# TB-S5D5_p05_JLink_OB-S124_QFP-v1_2.net
KiCad netlist of a schematic drawn in Altium Designer
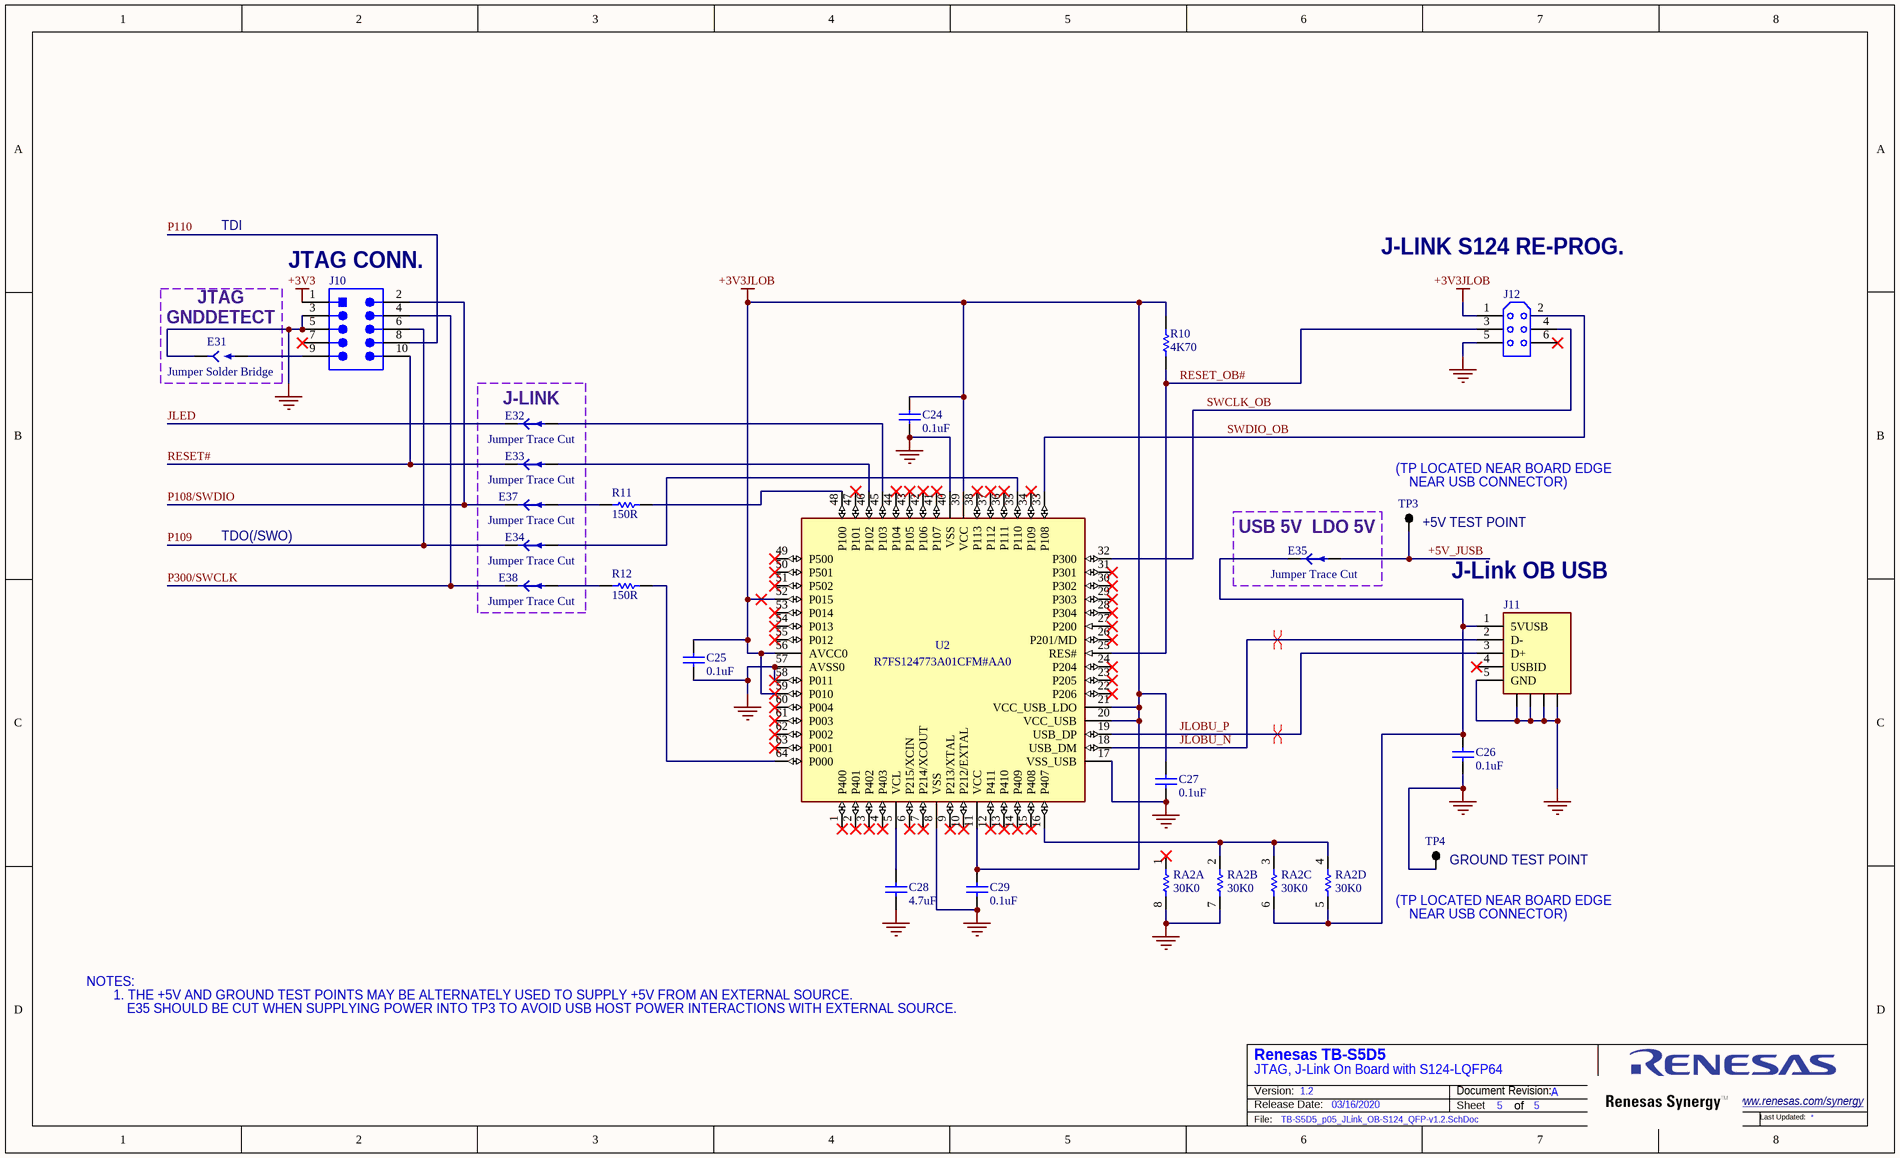
[diagram p0: TB-S5D5_p05_JLink_OB-S124_QFP-v1.2.SchDoc]

(export (version "E")
  (design (tool "Eeschema 10.0.6"))
  (components
    (comp (ref "C24")
      (value "CAP-000029-01")
      (footprint "CAPC0603-01")
      (description "Ceramic Chip Capacitor 0603 0.1uF 50V")
      (fields
        (field (name "MANUFACTURER") "Samsung")
        (field (name "MFG PART NUMBER") "CL10B104KB8NNNC")
        (field (name "CAPACITANCE") "0.1uF")
      )
      (libsource (lib "Capacitors") (part "CAP-000029-01"))
    )
    (comp (ref "C25")
      (value "CAP-000029-01")
      (footprint "CAPC0603-01")
      (description "Ceramic Chip Capacitor 0603 0.1uF 50V")
      (fields
        (field (name "MANUFACTURER") "Samsung")
        (field (name "MFG PART NUMBER") "CL10B104KB8NNNC")
        (field (name "CAPACITANCE") "0.1uF")
      )
      (libsource (lib "Capacitors") (part "CAP-000029-01"))
    )
    (comp (ref "C26")
      (value "CAP-000029-01")
      (footprint "CAPC0603-01")
      (description "Ceramic Chip Capacitor 0603 0.1uF 50V")
      (fields
        (field (name "MANUFACTURER") "Samsung")
        (field (name "MFG PART NUMBER") "CL10B104KB8NNNC")
        (field (name "CAPACITANCE") "0.1uF")
      )
      (libsource (lib "Capacitors") (part "CAP-000029-01"))
    )
    (comp (ref "C27")
      (value "CAP-000029-01")
      (footprint "CAPC0603-01")
      (description "Ceramic Chip Capacitor 0603 0.1uF 50V")
      (fields
        (field (name "MANUFACTURER") "Samsung")
        (field (name "MFG PART NUMBER") "CL10B104KB8NNNC")
        (field (name "CAPACITANCE") "0.1uF")
      )
      (libsource (lib "Capacitors") (part "CAP-000029-01"))
    )
    (comp (ref "C28")
      (value "CAP-000043-01")
      (footprint "CAPC0603-01")
      (description "Ceramic Chip Capacitor 0603 4.7uF 6.3V")
      (fields
        (field (name "MANUFACTURER") "Samsung")
        (field (name "MFG PART NUMBER") "CL10A475KQ8NNNL")
        (field (name "CAPACITANCE") "4.7uF")
      )
      (libsource (lib "Capacitors") (part "CAP-000043-01"))
    )
    (comp (ref "C29")
      (value "CAP-000029-01")
      (footprint "CAPC0603-01")
      (description "Ceramic Chip Capacitor 0603 0.1uF 50V")
      (fields
        (field (name "MANUFACTURER") "Samsung")
        (field (name "MFG PART NUMBER") "CL10B104KB8NNNC")
        (field (name "CAPACITANCE") "0.1uF")
      )
      (libsource (lib "Capacitors") (part "CAP-000029-01"))
    )
    (comp (ref "E31")
      (value "Jumper Solder Bridge")
      (footprint "E_PadsSplit0805")
      (description "Pads on PCB with Narrow Gap to allow Solder Bridging")
      (libsource (lib "TB_SpecialLib") (part "E_JmpSldrBridge"))
    )
    (comp (ref "E32")
      (value "Jumper Trace Cut")
      (footprint "E_PadsTraceCut0805")
      (description "Pads on PCB with Trace Between for Cutting to isolate")
      (libsource (lib "TB_SpecialLib") (part "E_JmpTraceCut"))
    )
    (comp (ref "E33")
      (value "Jumper Trace Cut")
      (footprint "E_PadsTraceCut0805")
      (description "Pads on PCB with Trace Between for Cutting to isolate")
      (libsource (lib "TB_SpecialLib") (part "E_JmpTraceCut"))
    )
    (comp (ref "E34")
      (value "Jumper Trace Cut")
      (footprint "E_PadsTraceCut0805")
      (description "Pads on PCB with Trace Between for Cutting to isolate")
      (libsource (lib "TB_SpecialLib") (part "E_JmpTraceCut"))
    )
    (comp (ref "E35")
      (value "Jumper Trace Cut")
      (footprint "E_PadsTraceCut0805")
      (description "Pads on PCB with Trace Between for Cutting to isolate")
      (libsource (lib "TB_SpecialLib") (part "E_JmpTraceCut"))
    )
    (comp (ref "E37")
      (value "Jumper Trace Cut")
      (footprint "E_PadsTraceCut0805")
      (description "Pads on PCB with Trace Between for Cutting to isolate")
      (libsource (lib "TB_SpecialLib") (part "E_JmpTraceCut"))
    )
    (comp (ref "E38")
      (value "Jumper Trace Cut")
      (footprint "E_PadsTraceCut0805")
      (description "Pads on PCB with Trace Between for Cutting to isolate")
      (libsource (lib "TB_SpecialLib") (part "E_JmpTraceCut"))
    )
    (comp (ref "J10")
      (value "CON-REN001-01")
      (footprint "J_10pTH2cx5r")
      (description "10 Position Shrouded Header 1.27mm Pitch")
      (fields (field (name "MANUFACTURER") "CNC Tech") (field (name "MFG PART NUMBER") "3220-10-0100-00"))
      (libsource (lib "SpecialPartsLib") (part "CON-REN001-01"))
    )
    (comp (ref "J11")
      (value "CON-000116-01")
      (footprint "FCI_10118192")
      (description "USB Micro 2.0 Female 5 Pin Right Angle")
      (fields (field (name "MANUFACTURER") "FCI") (field (name "MFG PART NUMBER") "10118192-0001LF"))
      (libsource (lib "Connectors") (part "CON-000116-01"))
    )
    (comp (ref "J12")
      (value "CON-000241-01")
      (footprint "TC2030NL")
      (description "Tag Connect TC-2030 PCB Pads 6 Pos 2x3")
      (libsource (lib "Connectors") (part "CON-000241-01"))
    )
    (comp (ref "R10")
      (value "RES-000127-01")
      (footprint "RESC0402-01")
      (description "Chip Resistor Thick Film 0402 4K70 0.5% 1/16W")
      (fields
        (field (name "MANUFACTURER") "Panasonic")
        (field (name "MFG PART NUMBER") "ERA-2AED472X")
        (field (name "RESISTANCE") "4K70")
      )
      (libsource (lib "Resistors") (part "RES-000127-01"))
    )
    (comp (ref "R11")
      (value "RES-000220-01")
      (footprint "RESC0402-01")
      (description "Chip Resistor Thick Film 0402 150R 1% 1/10W")
      (fields
        (field (name "MANUFACTURER") "Panasonic")
        (field (name "MFG PART NUMBER") "ERJ-2RKF1500X")
        (field (name "RESISTANCE") "150R")
      )
      (libsource (lib "Resistors") (part "RES-000220-01"))
    )
    (comp (ref "R12")
      (value "RES-000220-01")
      (footprint "RESC0402-01")
      (description "Chip Resistor Thick Film 0402 150R 1% 1/10W")
      (fields
        (field (name "MANUFACTURER") "Panasonic")
        (field (name "MFG PART NUMBER") "ERJ-2RKF1500X")
        (field (name "RESISTANCE") "150R")
      )
      (libsource (lib "Resistors") (part "RES-000220-01"))
    )
    (comp (ref "RA2")
      (value "RES-000117-01")
      (footprint "RESCAF0804")
      (description "Chip Resistor Array 0804 30K0 5% 1/16W 4 x 0402")
      (fields
        (field (name "MANUFACTURER") "Panasonic")
        (field (name "MFG PART NUMBER") "EXB-28V303JX")
        (field (name "RESISTANCE") "30K0")
      )
      (libsource (lib "Resistors") (part "RES-000117-01"))
    )
    (comp (ref "TP3")
      (value "Test Point")
      (footprint "TP_40milTHpad")
      (description "Test Point, Through Hole Pad 40mil ID")
      (libsource (lib "TB_SpecialLib") (part "TP_TH"))
    )
    (comp (ref "TP4")
      (value "Test Point")
      (footprint "TP_40milTHpad")
      (description "Test Point, Through Hole Pad 40mil ID")
      (libsource (lib "TB_SpecialLib") (part "TP_TH"))
    )
    (comp (ref "U2")
      (value "ICN-000202-01")
      (footprint "RENESAS_PLQP0064KB-A_N")
      (description "Renesas S124 32-Bit 32MHz Cortex M0+ MCU LQFP64")
      (fields
        (field (name "MANUFACTURER") "Renesas")
        (field (name "MFG PART NUMBER") "R7FS124773A01CFM#AA0")
        (field (name "DISPLAY NAME") "R7FS124773A01CFM#AA0")
      )
      (libsource (lib "IC_MCU") (part "ICN-000202-01"))
    )
  )
  (nets
    (net (code "1") (name "+3V3") (class "Default")
      (node (ref "J10") (pin "1") (pinfunction "1_1") (pintype "passive"))
    )
    (net (code "2") (name "+3V3JLOB") (class "Default")
      (node (ref "C24") (pin "2") (pinfunction "2_2") (pintype "passive"))
      (node (ref "C25") (pin "2") (pinfunction "2_2") (pintype "passive"))
      (node (ref "C27") (pin "2") (pinfunction "2_2") (pintype "passive"))
      (node (ref "C29") (pin "2") (pinfunction "2_2") (pintype "passive"))
      (node (ref "J12") (pin "1") (pinfunction "1_1") (pintype "passive"))
      (node (ref "R10") (pin "2") (pinfunction "2_2") (pintype "passive"))
      (node (ref "U2") (pin "11") (pinfunction "VCC_11") (pintype "power_in"))
      (node (ref "U2") (pin "20") (pinfunction "VCC_USB_20") (pintype "power_in"))
      (node (ref "U2") (pin "21") (pinfunction "VCC_USB_LDO_21") (pintype "power_in"))
      (node (ref "U2") (pin "39") (pinfunction "VCC_39") (pintype "power_in"))
      (node (ref "U2") (pin "52") (pinfunction "P015_52") (pintype "bidirectional"))
      (node (ref "U2") (pin "56") (pinfunction "AVCC0_56") (pintype "power_in"))
      (node (ref "U2") (pin "59") (pinfunction "P010_59") (pintype "bidirectional"))
    )
    (net (code "3") (name "/+5V_JUSB") (class "Default")
      (node (ref "E35") (pin "2") (pinfunction "A_2") (pintype "passive"))
      (node (ref "TP3") (pin "1") (pinfunction "TP_1") (pintype "passive"))
    )
    (net (code "4") (name "/JLED") (class "Default")
      (node (ref "E32") (pin "1") (pinfunction "A_1") (pintype "passive"))
    )
    (net (code "5") (name "/JLOBU_N") (class "Default")
      (node (ref "J11") (pin "2") (pinfunction "D-_2") (pintype "passive"))
      (node (ref "U2") (pin "18") (pinfunction "USB_DM_18") (pintype "bidirectional"))
    )
    (net (code "6") (name "/JLOBU_P") (class "Default")
      (node (ref "J11") (pin "3") (pinfunction "D+_3") (pintype "passive"))
      (node (ref "U2") (pin "19") (pinfunction "USB_DP_19") (pintype "bidirectional"))
    )
    (net (code "7") (name "/P108{slash}SWDIO") (class "Default")
      (node (ref "E37") (pin "1") (pinfunction "A_1") (pintype "passive"))
      (node (ref "J10") (pin "2") (pinfunction "2_2") (pintype "passive"))
    )
    (net (code "8") (name "/P109") (class "Default")
      (node (ref "E34") (pin "1") (pinfunction "A_1") (pintype "passive"))
      (node (ref "J10") (pin "6") (pinfunction "6_6") (pintype "passive"))
    )
    (net (code "9") (name "/P110") (class "Default")
      (node (ref "J10") (pin "8") (pinfunction "8_8") (pintype "passive"))
    )
    (net (code "10") (name "/P300{slash}SWCLK") (class "Default")
      (node (ref "E38") (pin "1") (pinfunction "A_1") (pintype "passive"))
      (node (ref "J10") (pin "4") (pinfunction "4_4") (pintype "passive"))
    )
    (net (code "11") (name "/RESET#") (class "Default")
      (node (ref "E33") (pin "1") (pinfunction "A_1") (pintype "passive"))
      (node (ref "J10") (pin "10") (pinfunction "10_10") (pintype "passive"))
    )
    (net (code "12") (name "/RESET_OB#") (class "Default")
      (node (ref "J12") (pin "3") (pinfunction "3_3") (pintype "passive"))
      (node (ref "R10") (pin "1") (pinfunction "1_1") (pintype "passive"))
      (node (ref "U2") (pin "25") (pinfunction "RES#_25") (pintype "input"))
    )
    (net (code "13") (name "/SWCLK_OB") (class "Default")
      (node (ref "J12") (pin "4") (pinfunction "4_4") (pintype "passive"))
      (node (ref "U2") (pin "32") (pinfunction "P300_32") (pintype "bidirectional"))
    )
    (net (code "14") (name "/SWDIO_OB") (class "Default")
      (node (ref "J12") (pin "2") (pinfunction "2_2") (pintype "passive"))
      (node (ref "U2") (pin "33") (pinfunction "P108_33") (pintype "bidirectional"))
    )
    (net (code "15") (name "GND") (class "Default")
      (node (ref "C24") (pin "1") (pinfunction "1_1") (pintype "passive"))
      (node (ref "C25") (pin "1") (pinfunction "1_1") (pintype "passive"))
      (node (ref "C26") (pin "1") (pinfunction "1_1") (pintype "passive"))
      (node (ref "C27") (pin "1") (pinfunction "1_1") (pintype "passive"))
      (node (ref "C28") (pin "2") (pinfunction "2_2") (pintype "passive"))
      (node (ref "C29") (pin "1") (pinfunction "1_1") (pintype "passive"))
      (node (ref "E31") (pin "1") (pinfunction "A_1") (pintype "passive"))
      (node (ref "J10") (pin "3") (pinfunction "3_3") (pintype "passive"))
      (node (ref "J10") (pin "5") (pinfunction "5_5") (pintype "passive"))
      (node (ref "J11") (pin "5") (pinfunction "GND_5") (pintype "passive"))
      (node (ref "J11") (pin "C1") (pinfunction "C1_C1") (pintype "passive"))
      (node (ref "J11") (pin "C2") (pinfunction "C2_C2") (pintype "passive"))
      (node (ref "J11") (pin "C3") (pinfunction "C3_C3") (pintype "passive"))
      (node (ref "J11") (pin "C4") (pinfunction "C4_C4") (pintype "passive"))
      (node (ref "J12") (pin "5") (pinfunction "5_5") (pintype "passive"))
      (node (ref "RA2") (pin "7") (pinfunction "7_7") (pintype "passive"))
      (node (ref "RA2") (pin "8") (pinfunction "8_8") (pintype "passive"))
      (node (ref "TP4") (pin "1") (pinfunction "TP_1") (pintype "passive"))
      (node (ref "U2") (pin "17") (pinfunction "VSS_USB_17") (pintype "power_in"))
      (node (ref "U2") (pin "40") (pinfunction "VSS_40") (pintype "power_in"))
      (node (ref "U2") (pin "57") (pinfunction "AVSS0_57") (pintype "power_in"))
      (node (ref "U2") (pin "58") (pinfunction "P011_58") (pintype "bidirectional"))
      (node (ref "U2") (pin "8") (pinfunction "VSS_8") (pintype "power_in"))
    )
    (net (code "16") (name "Net-(E31-A-Pad2)") (class "Default")
      (node (ref "E31") (pin "2") (pinfunction "A_2") (pintype "passive"))
      (node (ref "J10") (pin "9") (pinfunction "9_9") (pintype "passive"))
    )
    (net (code "17") (name "Net-(E37-A-Pad2)") (class "Default")
      (node (ref "E37") (pin "2") (pinfunction "A_2") (pintype "passive"))
      (node (ref "R11") (pin "1") (pinfunction "1_1") (pintype "passive"))
    )
    (net (code "18") (name "Net-(E38-A-Pad2)") (class "Default")
      (node (ref "E38") (pin "2") (pinfunction "A_2") (pintype "passive"))
      (node (ref "R12") (pin "1") (pinfunction "1_1") (pintype "passive"))
    )
    (net (code "19") (name "Net-(J11-5VUSB)") (class "Default")
      (node (ref "C26") (pin "2") (pinfunction "2_2") (pintype "passive"))
      (node (ref "E35") (pin "1") (pinfunction "A_1") (pintype "passive"))
      (node (ref "J11") (pin "1") (pinfunction "5VUSB_1") (pintype "passive"))
      (node (ref "RA2") (pin "5") (pinfunction "5_5") (pintype "passive"))
      (node (ref "RA2") (pin "6") (pinfunction "6_6") (pintype "passive"))
    )
    (net (code "20") (name "Net-(U2-P000)") (class "Default")
      (node (ref "R12") (pin "2") (pinfunction "2_2") (pintype "passive"))
      (node (ref "U2") (pin "64") (pinfunction "P000_64") (pintype "bidirectional"))
    )
    (net (code "21") (name "Net-(U2-P100)") (class "Default")
      (node (ref "R11") (pin "2") (pinfunction "2_2") (pintype "passive"))
      (node (ref "U2") (pin "48") (pinfunction "P100_48") (pintype "bidirectional"))
    )
    (net (code "22") (name "Net-(U2-P102)") (class "Default")
      (node (ref "E33") (pin "2") (pinfunction "A_2") (pintype "passive"))
      (node (ref "U2") (pin "46") (pinfunction "P102_46") (pintype "bidirectional"))
    )
    (net (code "23") (name "Net-(U2-P103)") (class "Default")
      (node (ref "E32") (pin "2") (pinfunction "A_2") (pintype "passive"))
      (node (ref "U2") (pin "45") (pinfunction "P103_45") (pintype "bidirectional"))
    )
    (net (code "24") (name "Net-(U2-P110)") (class "Default")
      (node (ref "E34") (pin "2") (pinfunction "A_2") (pintype "passive"))
      (node (ref "U2") (pin "35") (pinfunction "P110_35") (pintype "bidirectional"))
    )
    (net (code "25") (name "Net-(U2-P407)") (class "Default")
      (node (ref "RA2") (pin "2") (pinfunction "2_2") (pintype "passive"))
      (node (ref "RA2") (pin "3") (pinfunction "3_3") (pintype "passive"))
      (node (ref "RA2") (pin "4") (pinfunction "4_4") (pintype "passive"))
      (node (ref "U2") (pin "16") (pinfunction "P407_16") (pintype "bidirectional"))
    )
    (net (code "26") (name "Net-(U2-VCL)") (class "Default")
      (node (ref "C28") (pin "1") (pinfunction "1_1") (pintype "passive"))
      (node (ref "U2") (pin "5") (pinfunction "VCL_5") (pintype "passive"))
    )
    (net (code "27") (name "unconnected-(J10-Pad7)") (class "Default")
      (node (ref "J10") (pin "7") (pinfunction "7_7") (pintype "passive+no_connect"))
    )
    (net (code "28") (name "unconnected-(J11-USBID-Pad4)") (class "Default")
      (node (ref "J11") (pin "4") (pinfunction "USBID_4") (pintype "passive+no_connect"))
    )
    (net (code "29") (name "unconnected-(J12-Pad6)") (class "Default")
      (node (ref "J12") (pin "6") (pinfunction "6_6") (pintype "passive+no_connect"))
    )
    (net (code "30") (name "unconnected-(RA2-Pad1)") (class "Default")
      (node (ref "RA2") (pin "1") (pinfunction "1_1") (pintype "passive+no_connect"))
    )
    (net (code "31") (name "unconnected-(U2-P001-Pad63)") (class "Default")
      (node (ref "U2") (pin "63") (pinfunction "P001_63") (pintype "bidirectional+no_connect"))
    )
    (net (code "32") (name "unconnected-(U2-P002-Pad62)") (class "Default")
      (node (ref "U2") (pin "62") (pinfunction "P002_62") (pintype "bidirectional+no_connect"))
    )
    (net (code "33") (name "unconnected-(U2-P003-Pad61)") (class "Default")
      (node (ref "U2") (pin "61") (pinfunction "P003_61") (pintype "bidirectional+no_connect"))
    )
    (net (code "34") (name "unconnected-(U2-P004-Pad60)") (class "Default")
      (node (ref "U2") (pin "60") (pinfunction "P004_60") (pintype "bidirectional+no_connect"))
    )
    (net (code "35") (name "unconnected-(U2-P012-Pad55)") (class "Default")
      (node (ref "U2") (pin "55") (pinfunction "P012_55") (pintype "bidirectional+no_connect"))
    )
    (net (code "36") (name "unconnected-(U2-P013-Pad54)") (class "Default")
      (node (ref "U2") (pin "54") (pinfunction "P013_54") (pintype "bidirectional+no_connect"))
    )
    (net (code "37") (name "unconnected-(U2-P014-Pad53)") (class "Default")
      (node (ref "U2") (pin "53") (pinfunction "P014_53") (pintype "bidirectional+no_connect"))
    )
    (net (code "38") (name "unconnected-(U2-P101-Pad47)") (class "Default")
      (node (ref "U2") (pin "47") (pinfunction "P101_47") (pintype "bidirectional+no_connect"))
    )
    (net (code "39") (name "unconnected-(U2-P104-Pad44)") (class "Default")
      (node (ref "U2") (pin "44") (pinfunction "P104_44") (pintype "bidirectional+no_connect"))
    )
    (net (code "40") (name "unconnected-(U2-P105-Pad43)") (class "Default")
      (node (ref "U2") (pin "43") (pinfunction "P105_43") (pintype "bidirectional+no_connect"))
    )
    (net (code "41") (name "unconnected-(U2-P106-Pad42)") (class "Default")
      (node (ref "U2") (pin "42") (pinfunction "P106_42") (pintype "bidirectional+no_connect"))
    )
    (net (code "42") (name "unconnected-(U2-P107-Pad41)") (class "Default")
      (node (ref "U2") (pin "41") (pinfunction "P107_41") (pintype "bidirectional+no_connect"))
    )
    (net (code "43") (name "unconnected-(U2-P109-Pad34)") (class "Default")
      (node (ref "U2") (pin "34") (pinfunction "P109_34") (pintype "bidirectional+no_connect"))
    )
    (net (code "44") (name "unconnected-(U2-P111-Pad36)") (class "Default")
      (node (ref "U2") (pin "36") (pinfunction "P111_36") (pintype "bidirectional+no_connect"))
    )
    (net (code "45") (name "unconnected-(U2-P112-Pad37)") (class "Default")
      (node (ref "U2") (pin "37") (pinfunction "P112_37") (pintype "bidirectional+no_connect"))
    )
    (net (code "46") (name "unconnected-(U2-P113-Pad38)") (class "Default")
      (node (ref "U2") (pin "38") (pinfunction "P113_38") (pintype "bidirectional+no_connect"))
    )
    (net (code "47") (name "unconnected-(U2-P200-Pad27)") (class "Default")
      (node (ref "U2") (pin "27") (pinfunction "P200_27") (pintype "input+no_connect"))
    )
    (net (code "48") (name "unconnected-(U2-P201{slash}MD-Pad26)") (class "Default")
      (node (ref "U2") (pin "26") (pinfunction "P201/MD_26") (pintype "bidirectional+no_connect"))
    )
    (net (code "49") (name "unconnected-(U2-P204-Pad24)") (class "Default")
      (node (ref "U2") (pin "24") (pinfunction "P204_24") (pintype "bidirectional+no_connect"))
    )
    (net (code "50") (name "unconnected-(U2-P205-Pad23)") (class "Default")
      (node (ref "U2") (pin "23") (pinfunction "P205_23") (pintype "bidirectional+no_connect"))
    )
    (net (code "51") (name "unconnected-(U2-P206-Pad22)") (class "Default")
      (node (ref "U2") (pin "22") (pinfunction "P206_22") (pintype "bidirectional+no_connect"))
    )
    (net (code "52") (name "unconnected-(U2-P212{slash}EXTAL-Pad10)") (class "Default")
      (node (ref "U2") (pin "10") (pinfunction "P212/EXTAL_10") (pintype "bidirectional+no_connect"))
    )
    (net (code "53") (name "unconnected-(U2-P213{slash}XTAL-Pad9)") (class "Default")
      (node (ref "U2") (pin "9") (pinfunction "P213/XTAL_9") (pintype "bidirectional+no_connect"))
    )
    (net (code "54") (name "unconnected-(U2-P214{slash}XCOUT-Pad7)") (class "Default")
      (node (ref "U2") (pin "7") (pinfunction "P214/XCOUT_7") (pintype "bidirectional+no_connect"))
    )
    (net (code "55") (name "unconnected-(U2-P215{slash}XCIN-Pad6)") (class "Default")
      (node (ref "U2") (pin "6") (pinfunction "P215/XCIN_6") (pintype "bidirectional+no_connect"))
    )
    (net (code "56") (name "unconnected-(U2-P301-Pad31)") (class "Default")
      (node (ref "U2") (pin "31") (pinfunction "P301_31") (pintype "bidirectional+no_connect"))
    )
    (net (code "57") (name "unconnected-(U2-P302-Pad30)") (class "Default")
      (node (ref "U2") (pin "30") (pinfunction "P302_30") (pintype "bidirectional+no_connect"))
    )
    (net (code "58") (name "unconnected-(U2-P303-Pad29)") (class "Default")
      (node (ref "U2") (pin "29") (pinfunction "P303_29") (pintype "bidirectional+no_connect"))
    )
    (net (code "59") (name "unconnected-(U2-P304-Pad28)") (class "Default")
      (node (ref "U2") (pin "28") (pinfunction "P304_28") (pintype "bidirectional+no_connect"))
    )
    (net (code "60") (name "unconnected-(U2-P400-Pad1)") (class "Default")
      (node (ref "U2") (pin "1") (pinfunction "P400_1") (pintype "bidirectional+no_connect"))
    )
    (net (code "61") (name "unconnected-(U2-P401-Pad2)") (class "Default")
      (node (ref "U2") (pin "2") (pinfunction "P401_2") (pintype "bidirectional+no_connect"))
    )
    (net (code "62") (name "unconnected-(U2-P402-Pad3)") (class "Default")
      (node (ref "U2") (pin "3") (pinfunction "P402_3") (pintype "bidirectional+no_connect"))
    )
    (net (code "63") (name "unconnected-(U2-P403-Pad4)") (class "Default")
      (node (ref "U2") (pin "4") (pinfunction "P403_4") (pintype "bidirectional+no_connect"))
    )
    (net (code "64") (name "unconnected-(U2-P408-Pad15)") (class "Default")
      (node (ref "U2") (pin "15") (pinfunction "P408_15") (pintype "bidirectional+no_connect"))
    )
    (net (code "65") (name "unconnected-(U2-P409-Pad14)") (class "Default")
      (node (ref "U2") (pin "14") (pinfunction "P409_14") (pintype "bidirectional+no_connect"))
    )
    (net (code "66") (name "unconnected-(U2-P410-Pad13)") (class "Default")
      (node (ref "U2") (pin "13") (pinfunction "P410_13") (pintype "bidirectional+no_connect"))
    )
    (net (code "67") (name "unconnected-(U2-P411-Pad12)") (class "Default")
      (node (ref "U2") (pin "12") (pinfunction "P411_12") (pintype "bidirectional+no_connect"))
    )
    (net (code "68") (name "unconnected-(U2-P500-Pad49)") (class "Default")
      (node (ref "U2") (pin "49") (pinfunction "P500_49") (pintype "bidirectional+no_connect"))
    )
    (net (code "69") (name "unconnected-(U2-P501-Pad50)") (class "Default")
      (node (ref "U2") (pin "50") (pinfunction "P501_50") (pintype "bidirectional+no_connect"))
    )
    (net (code "70") (name "unconnected-(U2-P502-Pad51)") (class "Default")
      (node (ref "U2") (pin "51") (pinfunction "P502_51") (pintype "bidirectional+no_connect"))
    )
  )
)
